# flyback.net
KiCad netlist of a schematic drawn in Altium Designer
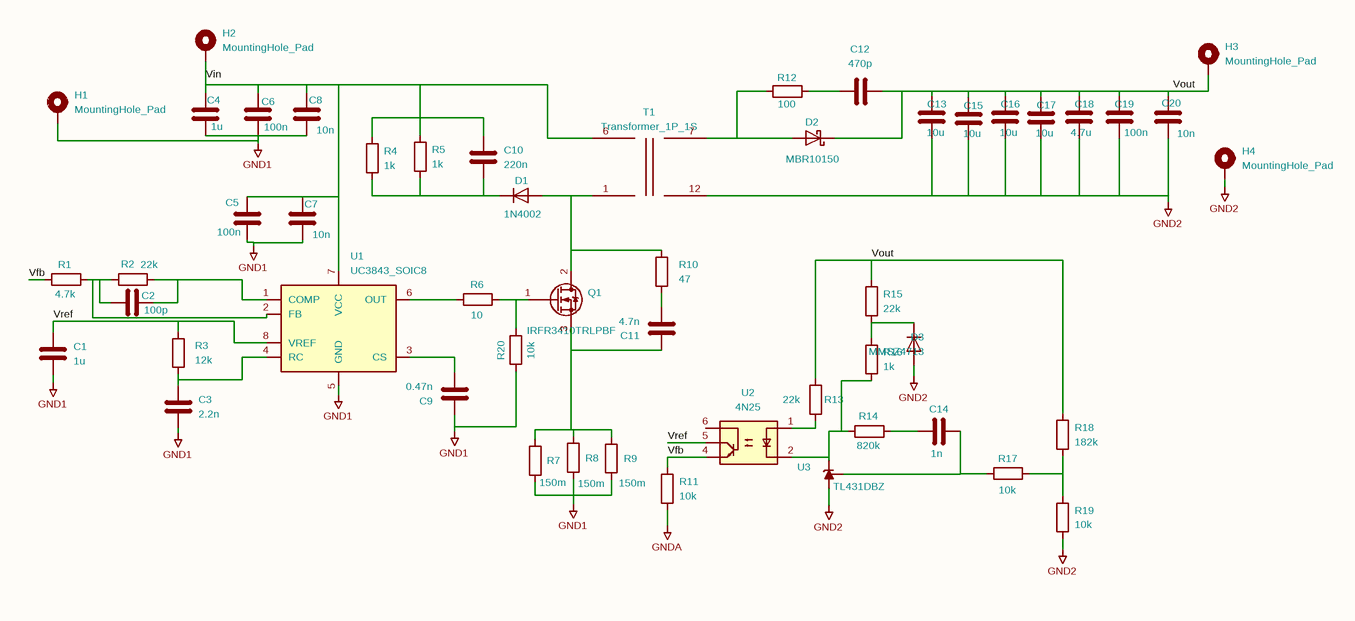
[diagram p0: flyback.SchDoc]

(export (version "E")
  (design (tool "Eeschema 10.0.6"))
  (components
    (comp (ref "C1") (value "1u") (libsource (lib "Device") (part "C")))
    (comp (ref "C2") (value "100p") (libsource (lib "Device") (part "C")))
    (comp (ref "C3") (value "2.2n") (libsource (lib "Device") (part "C")))
    (comp (ref "C4") (value "1u") (libsource (lib "Device") (part "C")))
    (comp (ref "C5") (value "100n") (libsource (lib "Device") (part "C")))
    (comp (ref "C6") (value "100n") (libsource (lib "Device") (part "C")))
    (comp (ref "C7") (value "10n") (libsource (lib "Device") (part "C")))
    (comp (ref "C8") (value "10n") (libsource (lib "Device") (part "C")))
    (comp (ref "C9") (value "0.47n") (libsource (lib "Device") (part "C")))
    (comp (ref "C10") (value "220n") (libsource (lib "Device") (part "C")))
    (comp (ref "C11") (value "4.7n") (libsource (lib "Device") (part "C")))
    (comp (ref "C12") (value "470p") (libsource (lib "Device") (part "C")))
    (comp (ref "C13") (value "10u") (libsource (lib "Device") (part "C")))
    (comp (ref "C14") (value "1n") (libsource (lib "Device") (part "C")))
    (comp (ref "C15") (value "10u") (libsource (lib "Device") (part "C")))
    (comp (ref "C16") (value "10u") (libsource (lib "Device") (part "C")))
    (comp (ref "C17") (value "10u") (libsource (lib "Device") (part "C")))
    (comp (ref "C18") (value "4.7u") (libsource (lib "Device") (part "C")))
    (comp (ref "C19") (value "100n") (libsource (lib "Device") (part "C")))
    (comp (ref "C20") (value "10n") (libsource (lib "Device") (part "C")))
    (comp (ref "D1") (value "1N4002") (libsource (lib "Diode") (part "1N4002")))
    (comp (ref "D2") (value "MBR10150") (libsource (lib "Diode") (part "MBR735")))
    (comp (ref "D3") (value "MMSZ4713") (libsource (lib "Diode") (part "MMSD4148")))
    (comp (ref "H1") (value "MountingHole_Pad") (libsource (lib "Mechanical") (part "MountingHole_Pad")))
    (comp (ref "H2") (value "MountingHole_Pad") (libsource (lib "Mechanical") (part "MountingHole_Pad")))
    (comp (ref "H3") (value "MountingHole_Pad") (libsource (lib "Mechanical") (part "MountingHole_Pad")))
    (comp (ref "H4") (value "MountingHole_Pad") (libsource (lib "Mechanical") (part "MountingHole_Pad")))
    (comp (ref "Q1") (value "IRFR3410TRLPBF") (libsource (lib "Transistor_FET") (part "QM6006D")))
    (comp (ref "R1") (value "4.7k") (libsource (lib "") (part "R_1")))
    (comp (ref "R2") (value "22k") (libsource (lib "") (part "R_1")))
    (comp (ref "R3") (value "12k") (libsource (lib "Device") (part "R")))
    (comp (ref "R4") (value "1k") (libsource (lib "Device") (part "R")))
    (comp (ref "R5") (value "1k") (libsource (lib "Device") (part "R")))
    (comp (ref "R6") (value "10") (libsource (lib "") (part "R_1")))
    (comp (ref "R7") (value "150m") (libsource (lib "Device") (part "R")))
    (comp (ref "R8") (value "150m") (libsource (lib "Device") (part "R")))
    (comp (ref "R9") (value "150m") (libsource (lib "Device") (part "R")))
    (comp (ref "R10") (value "47") (libsource (lib "Device") (part "R")))
    (comp (ref "R11") (value "10k") (libsource (lib "Device") (part "R")))
    (comp (ref "R12") (value "100") (libsource (lib "") (part "R_1")))
    (comp (ref "R13") (value "22k") (libsource (lib "Device") (part "R")))
    (comp (ref "R14") (value "820k") (libsource (lib "") (part "R_1")))
    (comp (ref "R15") (value "22k") (libsource (lib "Device") (part "R")))
    (comp (ref "R16") (value "1k") (libsource (lib "Device") (part "R")))
    (comp (ref "R17") (value "10k") (libsource (lib "") (part "R_1")))
    (comp (ref "R18") (value "182k") (libsource (lib "Device") (part "R")))
    (comp (ref "R19") (value "10k") (libsource (lib "Device") (part "R")))
    (comp (ref "R20") (value "10k") (libsource (lib "") (part "R_2")))
    (comp (ref "T1") (value "Transformer_1P_1S") (libsource (lib "Device") (part "Transformer_1P_1S")))
    (comp (ref "U1") (value "UC3843_SOIC8") (libsource (lib "Regulator_Controller") (part "UC3843_SOIC8")))
    (comp (ref "U2") (value "4N25") (libsource (lib "Isolator") (part "4N25")))
    (comp (ref "U3") (value "TL431DBZ") (libsource (lib "Reference_Voltage") (part "TL431DBZ")))
  )
  (nets
    (net (code "1") (name "/Vfb") (class "Default")
      (node (ref "R1") (pin "1") (pinfunction "1_1") (pintype "passive"))
      (node (ref "R11") (pin "1") (pinfunction "1_1") (pintype "passive"))
      (node (ref "U2") (pin "4") (pinfunction "4_4") (pintype "passive"))
    )
    (net (code "2") (name "/Vin") (class "Default")
      (node (ref "C10") (pin "1") (pinfunction "1_1") (pintype "passive"))
      (node (ref "C4") (pin "2") (pinfunction "2_2") (pintype "passive"))
      (node (ref "C5") (pin "2") (pinfunction "2_2") (pintype "passive"))
      (node (ref "C6") (pin "2") (pinfunction "2_2") (pintype "passive"))
      (node (ref "C7") (pin "2") (pinfunction "2_2") (pintype "passive"))
      (node (ref "C8") (pin "2") (pinfunction "2_2") (pintype "passive"))
      (node (ref "H2") (pin "1") (pinfunction "1_1") (pintype "passive"))
      (node (ref "R4") (pin "1") (pinfunction "1_1") (pintype "passive"))
      (node (ref "R5") (pin "1") (pinfunction "1_1") (pintype "passive"))
      (node (ref "T1") (pin "6") (pinfunction "AA_6") (pintype "passive"))
      (node (ref "U1") (pin "7") (pinfunction "VCC_7") (pintype "passive"))
    )
    (net (code "3") (name "/Vout") (class "Default")
      (node (ref "C12") (pin "2") (pinfunction "2_2") (pintype "passive"))
      (node (ref "C13") (pin "2") (pinfunction "2_2") (pintype "passive"))
      (node (ref "C15") (pin "2") (pinfunction "2_2") (pintype "passive"))
      (node (ref "C16") (pin "2") (pinfunction "2_2") (pintype "passive"))
      (node (ref "C17") (pin "2") (pinfunction "2_2") (pintype "passive"))
      (node (ref "C18") (pin "2") (pinfunction "2_2") (pintype "passive"))
      (node (ref "C19") (pin "2") (pinfunction "2_2") (pintype "passive"))
      (node (ref "C20") (pin "2") (pinfunction "2_2") (pintype "passive"))
      (node (ref "D2") (pin "1") (pinfunction "K_1") (pintype "passive"))
      (node (ref "H3") (pin "1") (pinfunction "1_1") (pintype "passive"))
      (node (ref "R13") (pin "1") (pinfunction "1_1") (pintype "passive"))
      (node (ref "R15") (pin "1") (pinfunction "1_1") (pintype "passive"))
      (node (ref "R18") (pin "1") (pinfunction "1_1") (pintype "passive"))
    )
    (net (code "4") (name "/Vref") (class "Default")
      (node (ref "C1") (pin "1") (pinfunction "1_1") (pintype "passive"))
      (node (ref "R3") (pin "1") (pinfunction "1_1") (pintype "passive"))
      (node (ref "U1") (pin "8") (pinfunction "VREF_8") (pintype "passive"))
      (node (ref "U2") (pin "5") (pinfunction "5_5") (pintype "passive"))
    )
    (net (code "5") (name "GND1") (class "Default")
      (node (ref "C1") (pin "2") (pinfunction "2_2") (pintype "passive"))
      (node (ref "C3") (pin "2") (pinfunction "2_2") (pintype "passive"))
      (node (ref "C4") (pin "1") (pinfunction "1_1") (pintype "passive"))
      (node (ref "C5") (pin "1") (pinfunction "1_1") (pintype "passive"))
      (node (ref "C6") (pin "1") (pinfunction "1_1") (pintype "passive"))
      (node (ref "C7") (pin "1") (pinfunction "1_1") (pintype "passive"))
      (node (ref "C8") (pin "1") (pinfunction "1_1") (pintype "passive"))
      (node (ref "C9") (pin "1") (pinfunction "1_1") (pintype "passive"))
      (node (ref "H1") (pin "1") (pinfunction "1_1") (pintype "passive"))
      (node (ref "R20") (pin "1") (pinfunction "1_1") (pintype "passive"))
      (node (ref "R7") (pin "2") (pinfunction "2_2") (pintype "passive"))
      (node (ref "R8") (pin "2") (pinfunction "2_2") (pintype "passive"))
      (node (ref "R9") (pin "2") (pinfunction "2_2") (pintype "passive"))
      (node (ref "U1") (pin "5") (pinfunction "GND_5") (pintype "passive"))
    )
    (net (code "6") (name "GND2") (class "Default")
      (node (ref "C13") (pin "1") (pinfunction "1_1") (pintype "passive"))
      (node (ref "C15") (pin "1") (pinfunction "1_1") (pintype "passive"))
      (node (ref "C16") (pin "1") (pinfunction "1_1") (pintype "passive"))
      (node (ref "C17") (pin "1") (pinfunction "1_1") (pintype "passive"))
      (node (ref "C18") (pin "1") (pinfunction "1_1") (pintype "passive"))
      (node (ref "C19") (pin "1") (pinfunction "1_1") (pintype "passive"))
      (node (ref "C20") (pin "1") (pinfunction "1_1") (pintype "passive"))
      (node (ref "D3") (pin "2") (pinfunction "A_2") (pintype "passive"))
      (node (ref "H4") (pin "1") (pinfunction "1_1") (pintype "passive"))
      (node (ref "R19") (pin "2") (pinfunction "2_2") (pintype "passive"))
      (node (ref "T1") (pin "12") (pinfunction "SA_12") (pintype "passive"))
      (node (ref "U3") (pin "3") (pinfunction "A_3") (pintype "passive"))
    )
    (net (code "7") (name "GNDA") (class "Default")
      (node (ref "R11") (pin "2") (pinfunction "2_2") (pintype "passive"))
    )
    (net (code "8") (name "Net-(C11-Pad2)") (class "Default")
      (node (ref "C11") (pin "2") (pinfunction "2_2") (pintype "passive"))
      (node (ref "R10") (pin "2") (pinfunction "2_2") (pintype "passive"))
    )
    (net (code "9") (name "Net-(C12-Pad1)") (class "Default")
      (node (ref "C12") (pin "1") (pinfunction "1_1") (pintype "passive"))
      (node (ref "R12") (pin "2") (pinfunction "2_2") (pintype "passive"))
    )
    (net (code "10") (name "Net-(C14-Pad1)") (class "Default")
      (node (ref "C14") (pin "1") (pinfunction "1_1") (pintype "passive"))
      (node (ref "R14") (pin "2") (pinfunction "2_2") (pintype "passive"))
    )
    (net (code "11") (name "Net-(D1-A)") (class "Default")
      (node (ref "D1") (pin "2") (pinfunction "A_2") (pintype "passive"))
      (node (ref "Q1") (pin "2") (pinfunction "D_2") (pintype "passive"))
      (node (ref "R10") (pin "1") (pinfunction "1_1") (pintype "passive"))
      (node (ref "T1") (pin "1") (pinfunction "AB_1") (pintype "passive"))
    )
    (net (code "12") (name "Net-(D1-K)") (class "Default")
      (node (ref "C10") (pin "2") (pinfunction "2_2") (pintype "passive"))
      (node (ref "D1") (pin "1") (pinfunction "K_1") (pintype "passive"))
      (node (ref "R4") (pin "2") (pinfunction "2_2") (pintype "passive"))
      (node (ref "R5") (pin "2") (pinfunction "2_2") (pintype "passive"))
    )
    (net (code "13") (name "Net-(D2-A)") (class "Default")
      (node (ref "D2") (pin "2") (pinfunction "A_2") (pintype "passive"))
      (node (ref "R12") (pin "1") (pinfunction "1_1") (pintype "passive"))
      (node (ref "T1") (pin "7") (pinfunction "SB_7") (pintype "passive"))
    )
    (net (code "14") (name "Net-(D3-K)") (class "Default")
      (node (ref "D3") (pin "1") (pinfunction "K_1") (pintype "passive"))
      (node (ref "R15") (pin "2") (pinfunction "2_2") (pintype "passive"))
      (node (ref "R16") (pin "1") (pinfunction "1_1") (pintype "passive"))
    )
    (net (code "15") (name "Net-(Q1-G)") (class "Default")
      (node (ref "Q1") (pin "1") (pinfunction "G_1") (pintype "passive"))
      (node (ref "R20") (pin "2") (pinfunction "2_2") (pintype "passive"))
      (node (ref "R6") (pin "2") (pinfunction "2_2") (pintype "passive"))
    )
    (net (code "16") (name "Net-(Q1-S)") (class "Default")
      (node (ref "C11") (pin "1") (pinfunction "1_1") (pintype "passive"))
      (node (ref "Q1") (pin "3") (pinfunction "S_3") (pintype "passive"))
      (node (ref "R7") (pin "1") (pinfunction "1_1") (pintype "passive"))
      (node (ref "R8") (pin "1") (pinfunction "1_1") (pintype "passive"))
      (node (ref "R9") (pin "1") (pinfunction "1_1") (pintype "passive"))
    )
    (net (code "17") (name "Net-(R13-Pad2)") (class "Default")
      (node (ref "R13") (pin "2") (pinfunction "2_2") (pintype "passive"))
      (node (ref "U2") (pin "1") (pinfunction "1_1") (pintype "passive"))
    )
    (net (code "18") (name "Net-(R17-Pad2)") (class "Default")
      (node (ref "R17") (pin "2") (pinfunction "2_2") (pintype "passive"))
      (node (ref "R18") (pin "2") (pinfunction "2_2") (pintype "passive"))
      (node (ref "R19") (pin "1") (pinfunction "1_1") (pintype "passive"))
    )
    (net (code "19") (name "Net-(U1-COMP)") (class "Default")
      (node (ref "C2") (pin "2") (pinfunction "2_2") (pintype "passive"))
      (node (ref "R2") (pin "2") (pinfunction "2_2") (pintype "passive"))
      (node (ref "U1") (pin "1") (pinfunction "COMP_1") (pintype "passive"))
    )
    (net (code "20") (name "Net-(U1-CS)") (class "Default")
      (node (ref "C9") (pin "2") (pinfunction "2_2") (pintype "passive"))
      (node (ref "U1") (pin "3") (pinfunction "CS_3") (pintype "passive"))
    )
    (net (code "21") (name "Net-(U1-FB)") (class "Default")
      (node (ref "C2") (pin "1") (pinfunction "1_1") (pintype "passive"))
      (node (ref "R1") (pin "2") (pinfunction "2_2") (pintype "passive"))
      (node (ref "R2") (pin "1") (pinfunction "1_1") (pintype "passive"))
      (node (ref "U1") (pin "2") (pinfunction "FB_2") (pintype "passive"))
    )
    (net (code "22") (name "Net-(U1-OUT)") (class "Default")
      (node (ref "R6") (pin "1") (pinfunction "1_1") (pintype "passive"))
      (node (ref "U1") (pin "6") (pinfunction "OUT_6") (pintype "passive"))
    )
    (net (code "23") (name "Net-(U1-RC)") (class "Default")
      (node (ref "C3") (pin "1") (pinfunction "1_1") (pintype "passive"))
      (node (ref "R3") (pin "2") (pinfunction "2_2") (pintype "passive"))
      (node (ref "U1") (pin "4") (pinfunction "RC_4") (pintype "passive"))
    )
    (net (code "24") (name "Net-(U3-K)") (class "Default")
      (node (ref "R14") (pin "1") (pinfunction "1_1") (pintype "passive"))
      (node (ref "R16") (pin "2") (pinfunction "2_2") (pintype "passive"))
      (node (ref "U2") (pin "2") (pinfunction "2_2") (pintype "passive"))
      (node (ref "U3") (pin "1") (pinfunction "K_1") (pintype "passive"))
    )
    (net (code "25") (name "Net-(U3-REF)") (class "Default")
      (node (ref "C14") (pin "2") (pinfunction "2_2") (pintype "passive"))
      (node (ref "R17") (pin "1") (pinfunction "1_1") (pintype "passive"))
      (node (ref "U3") (pin "2") (pinfunction "REF_2") (pintype "passive"))
    )
    (net (code "26") (name "unconnected-(U2-NC-Pad3)") (class "Default")
      (node (ref "U2") (pin "3") (pinfunction "NC_3") (pintype "passive"))
    )
    (net (code "27") (name "unconnected-(U2-Pad6)") (class "Default")
      (node (ref "U2") (pin "6") (pinfunction "6_6") (pintype "passive"))
    )
  )
)
